# PLD_RadFET_LCL.net
KiCad netlist of a schematic drawn in Altium Designer
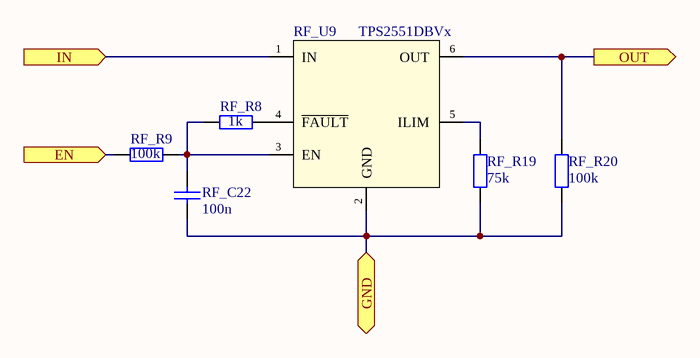
[diagram p0: PLD_RadFET_LCL.SchDoc]

(export (version "E")
  (design (tool "Eeschema 10.0.6"))
  (components
    (comp (ref "RF_C22")
      (value "100n")
      (footprint "SMD_Capacitor_0603")
      (description "Cap")
      (libsource (lib "capacitors") (part "Cap"))
    )
    (comp (ref "RF_R8")
      (value "1k")
      (footprint "SMD_Resistor_0603")
      (libsource (lib "resistors") (part "Res"))
    )
    (comp (ref "RF_R9")
      (value "100k")
      (footprint "SMD_Resistor_0603")
      (libsource (lib "resistors") (part "Res"))
    )
    (comp (ref "RF_R19") (value "75k") (footprint "SMD_Resistor_0603") (libsource (lib "") (part "Res_1")))
    (comp (ref "RF_R20") (value "100k") (footprint "SMD_Resistor_0603") (libsource (lib "") (part "Res_1")))
    (comp (ref "RF_U9")
      (value "TPS2551DBVx")
      (footprint "SOT23-6")
      (description "Adjustable Current-Limited Power-Distribution Switch.")
      (fields (field (name "MANUFACTURER") "Texas Instruments"))
      (libsource (lib "microcircuits") (part "TPS2551DBVx"))
    )
  )
  (nets
    (net (code "1") (name "/EN") (class "Default")
      (node (ref "RF_R9") (pin "2") (pinfunction "2_2") (pintype "passive"))
    )
    (net (code "2") (name "/GND") (class "Default")
      (node (ref "RF_C22") (pin "2") (pinfunction "2_2") (pintype "passive"))
      (node (ref "RF_R19") (pin "1") (pinfunction "1_1") (pintype "passive"))
      (node (ref "RF_R20") (pin "1") (pinfunction "1_1") (pintype "passive"))
      (node (ref "RF_U9") (pin "2") (pinfunction "GND_2") (pintype "passive"))
    )
    (net (code "3") (name "/IN") (class "Default")
      (node (ref "RF_U9") (pin "1") (pinfunction "IN_1") (pintype "passive"))
    )
    (net (code "4") (name "/OUT") (class "Default")
      (node (ref "RF_R20") (pin "2") (pinfunction "2_2") (pintype "passive"))
      (node (ref "RF_U9") (pin "6") (pinfunction "OUT_6") (pintype "passive"))
    )
    (net (code "5") (name "Net-(RF_U9-EN)") (class "Default")
      (node (ref "RF_C22") (pin "1") (pinfunction "1_1") (pintype "passive"))
      (node (ref "RF_R8") (pin "2") (pinfunction "2_2") (pintype "passive"))
      (node (ref "RF_R9") (pin "1") (pinfunction "1_1") (pintype "passive"))
      (node (ref "RF_U9") (pin "3") (pinfunction "EN_3") (pintype "passive"))
    )
    (net (code "6") (name "Net-(RF_U9-ILIM)") (class "Default")
      (node (ref "RF_R19") (pin "2") (pinfunction "2_2") (pintype "passive"))
      (node (ref "RF_U9") (pin "5") (pinfunction "ILIM_5") (pintype "passive"))
    )
    (net (code "7") (name "Net-(RF_U9-~{FAULT})") (class "Default")
      (node (ref "RF_R8") (pin "1") (pinfunction "1_1") (pintype "passive"))
      (node (ref "RF_U9") (pin "4") (pinfunction "~{FAULT}_4") (pintype "passive"))
    )
  )
)
